# 1_uC.net
KiCad netlist of a schematic drawn in Altium Designer
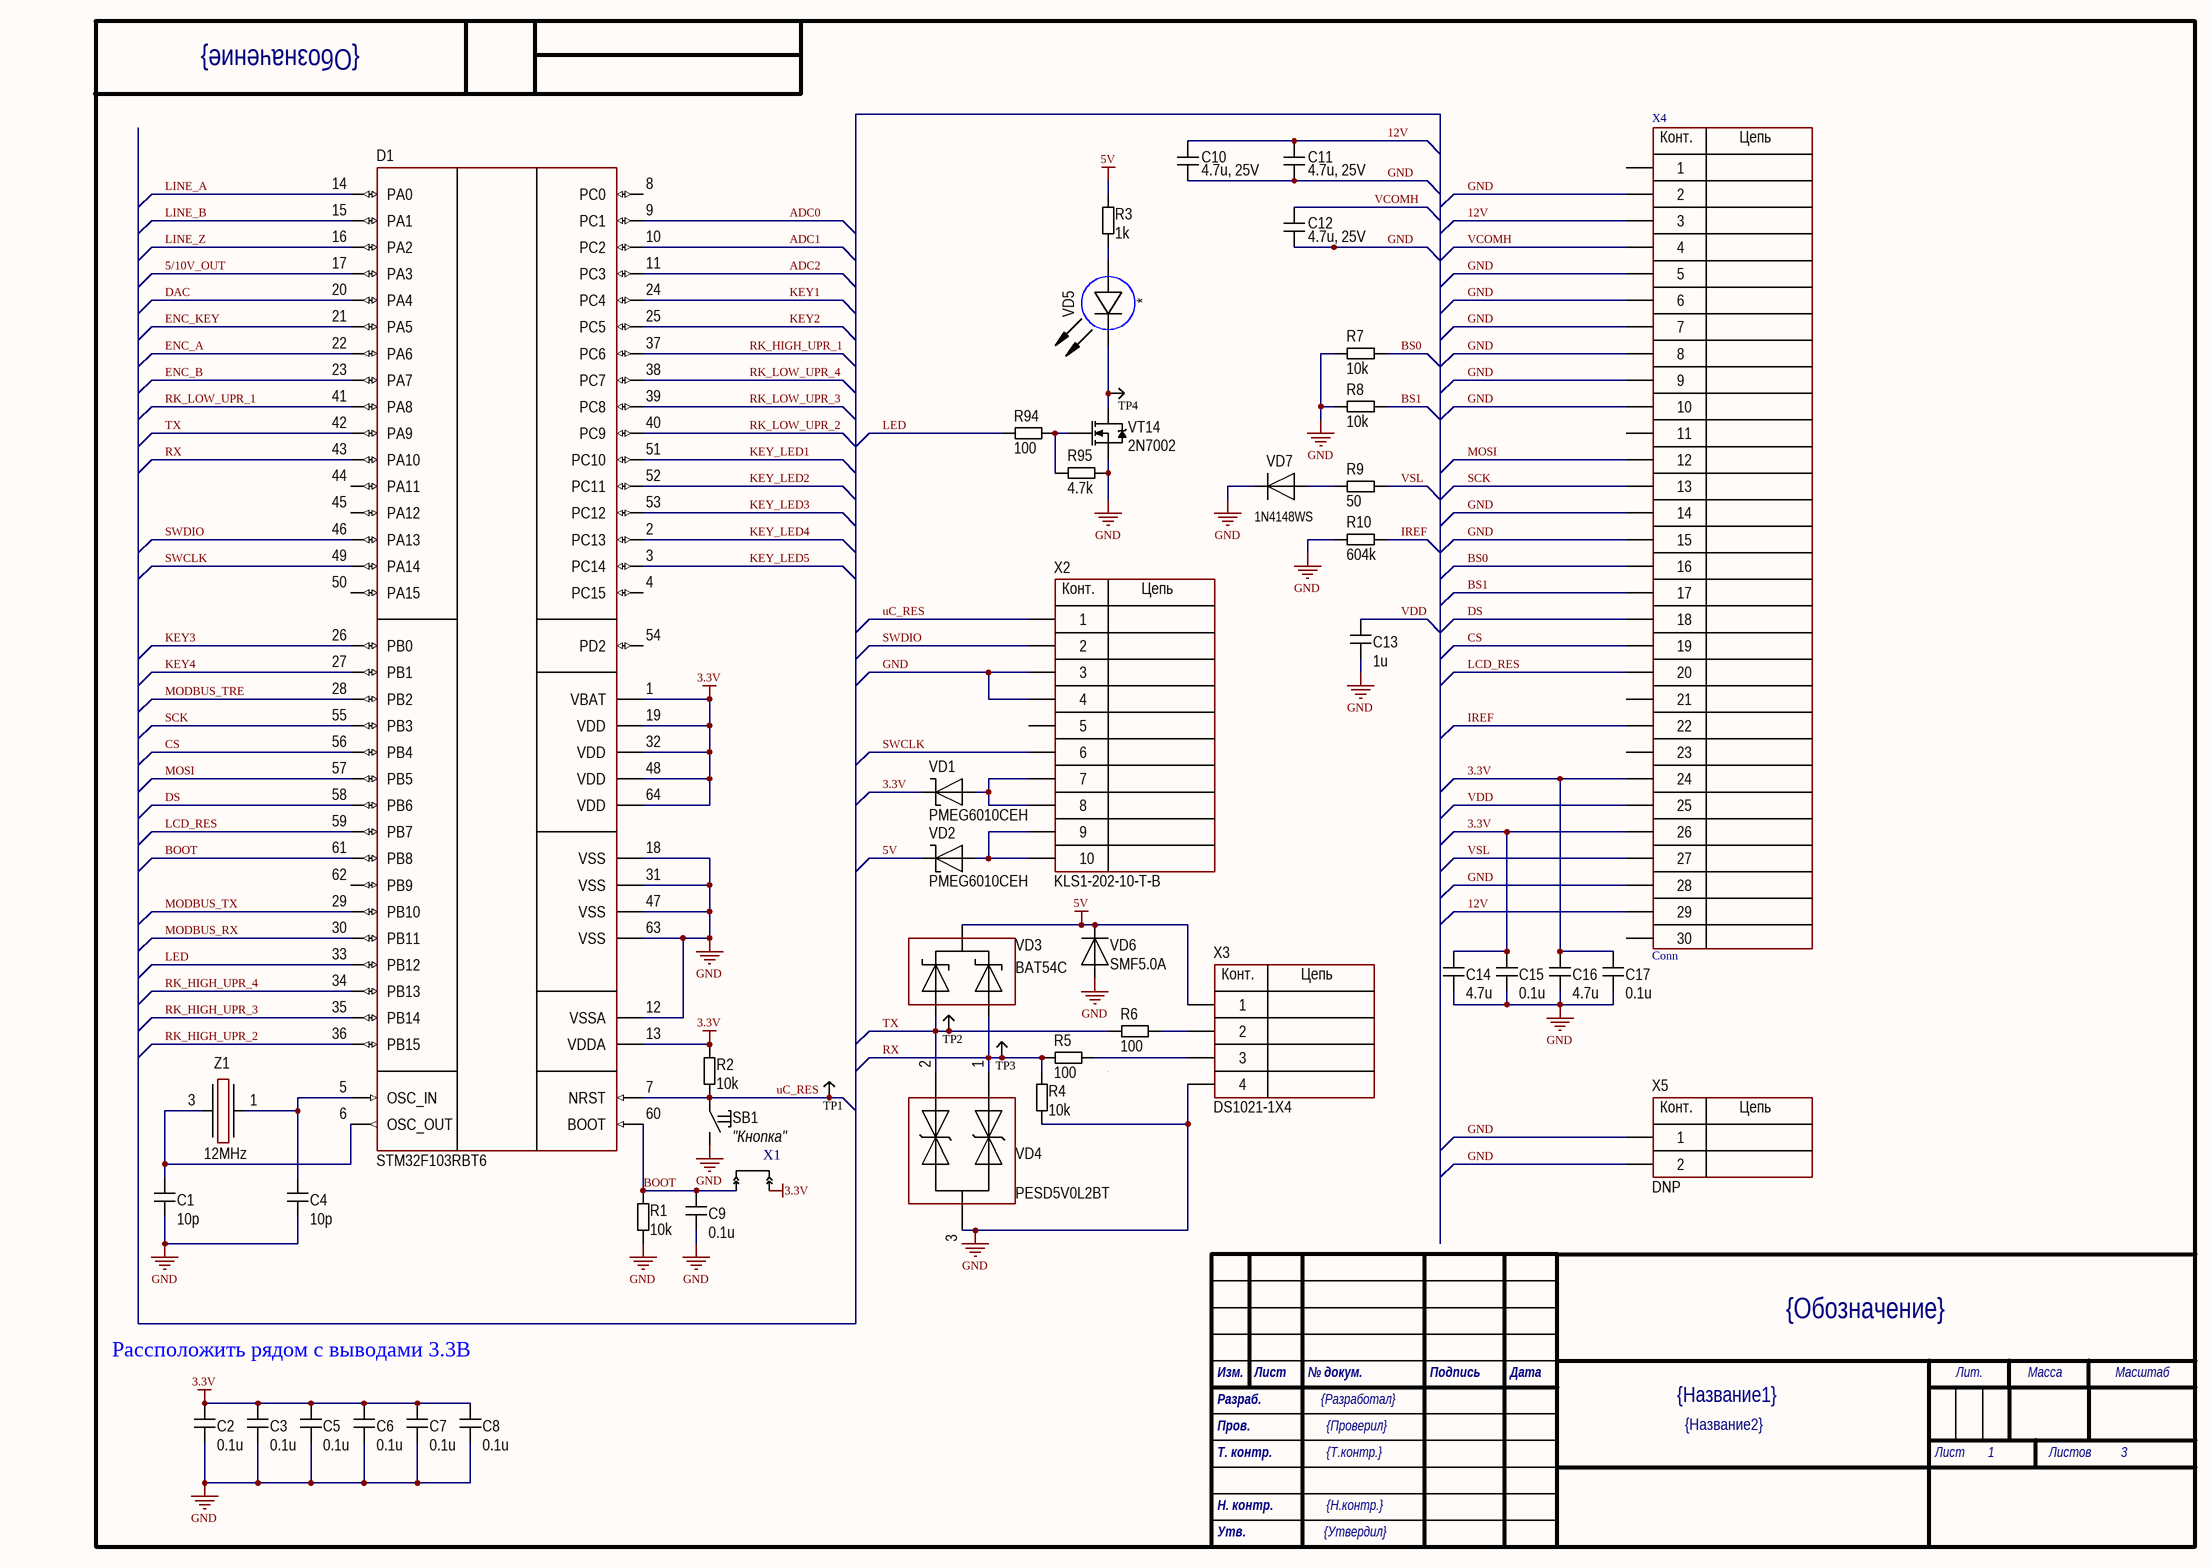
[diagram p0: 1_uC.SchDoc]

(export (version "E")
  (design (tool "Eeschema 10.0.6"))
  (components
    (comp (ref "C1") (value "10p") (footprint "CH0402C") (libsource (lib "Condensators") (part "Capacitor")))
    (comp (ref "C2") (value "0.1u") (footprint "CH0603C") (libsource (lib "Condensators") (part "Capacitor")))
    (comp (ref "C3") (value "0.1u") (footprint "CH0603C") (libsource (lib "Condensators") (part "Capacitor")))
    (comp (ref "C4") (value "10p") (footprint "CH0402C") (libsource (lib "Condensators") (part "Capacitor")))
    (comp (ref "C5") (value "0.1u") (footprint "CH0603C") (libsource (lib "Condensators") (part "Capacitor")))
    (comp (ref "C6") (value "0.1u") (footprint "CH0603C") (libsource (lib "Condensators") (part "Capacitor")))
    (comp (ref "C7") (value "0.1u") (footprint "CH0603C") (libsource (lib "Condensators") (part "Capacitor")))
    (comp (ref "C8") (value "0.1u") (footprint "CH0603C") (libsource (lib "Condensators") (part "Capacitor")))
    (comp (ref "C9") (value "0.1u") (footprint "CH0603C") (libsource (lib "Condensators") (part "Capacitor")))
    (comp (ref "C10")
      (value "4.7u, 25V")
      (footprint "CH0805C")
      (libsource (lib "Condensators") (part "Capacitor"))
    )
    (comp (ref "C11")
      (value "4.7u, 25V")
      (footprint "CH0805C")
      (libsource (lib "Condensators") (part "Capacitor"))
    )
    (comp (ref "C12")
      (value "4.7u, 25V")
      (footprint "CH0805C")
      (libsource (lib "Condensators") (part "Capacitor"))
    )
    (comp (ref "C13") (value "1u") (footprint "CH0603C") (libsource (lib "Condensators") (part "Capacitor")))
    (comp (ref "C14")
      (value "4.7u")
      (footprint "CH0603C")
      (libsource (lib "Condensators") (part "Capacitor"))
    )
    (comp (ref "C15")
      (value "0.1u")
      (footprint "CH0603C")
      (libsource (lib "Condensators") (part "Capacitor"))
    )
    (comp (ref "C16")
      (value "4.7u")
      (footprint "CH0603C")
      (libsource (lib "Condensators") (part "Capacitor"))
    )
    (comp (ref "C17")
      (value "0.1u")
      (footprint "CH0603C")
      (libsource (lib "Condensators") (part "Capacitor"))
    )
    (comp (ref "D1")
      (value "STM32F103RBT6")
      (footprint "64-LQFP")
      (description "Cortex-M3")
      (fields (field (name "MANUFACTURER") "STMicroelectronics"))
      (libsource (lib "MicroIC") (part "STM32F103RBT6"))
    )
    (comp (ref "R1") (value "10k") (footprint "CH0603R") (libsource (lib "Resistors") (part "Resistor")))
    (comp (ref "R2") (value "10k") (footprint "CH0603R") (libsource (lib "Resistors") (part "Resistor")))
    (comp (ref "R3") (value "1k") (footprint "CH0805R") (libsource (lib "Resistors") (part "Resistor")))
    (comp (ref "R4") (value "10k") (footprint "CH0603R") (libsource (lib "Resistors") (part "Resistor")))
    (comp (ref "R5") (value "100") (footprint "CH0603R") (libsource (lib "Resistors") (part "Resistor")))
    (comp (ref "R6") (value "100") (footprint "CH0603R") (libsource (lib "Resistors") (part "Resistor")))
    (comp (ref "R7") (value "10k") (footprint "CH0603R") (libsource (lib "Resistors") (part "Resistor")))
    (comp (ref "R8") (value "10k") (footprint "CH0603R") (libsource (lib "Resistors") (part "Resistor")))
    (comp (ref "R9") (value "50") (footprint "CH0603R") (libsource (lib "Resistors") (part "Resistor")))
    (comp (ref "R10") (value "604k") (footprint "CH0603R") (libsource (lib "Resistors") (part "Resistor")))
    (comp (ref "R94") (value "100") (footprint "CH0603R") (libsource (lib "Resistors") (part "Resistor")))
    (comp (ref "R95") (value "4.7k") (footprint "CH0603R") (libsource (lib "Resistors") (part "Resistor")))
    (comp (ref "SB1")
      (value "\"Кнопка\"")
      (footprint "TL1014BF160QG")
      (description "6x6 mm")
      (libsource (lib "Connectors") (part "Tactile switches"))
    )
    (comp (ref "TP1") (value "~") (footprint "TestPoint") (libsource (lib "Melochi") (part "TestPoint")))
    (comp (ref "TP2") (value "~") (footprint "TestPoint") (libsource (lib "Melochi") (part "TestPoint")))
    (comp (ref "TP3") (value "~") (footprint "TestPoint") (libsource (lib "Melochi") (part "TestPoint")))
    (comp (ref "TP4") (value "~") (footprint "TestPoint") (libsource (lib "Melochi") (part "TestPoint")))
    (comp (ref "VD1")
      (value "PMEG6010CEH")
      (footprint "SOD123F")
      (libsource (lib "Diods") (part "Diod Schottky"))
    )
    (comp (ref "VD2")
      (value "PMEG6010CEH")
      (footprint "SOD123F")
      (libsource (lib "Diods") (part "Diod Schottky"))
    )
    (comp (ref "VD3")
      (value "BAT54C")
      (footprint "SOT23_123")
      (libsource (lib "Diods") (part "Diod Schottky Array v.1"))
    )
    (comp (ref "VD4")
      (value "PESD5V0L2BT")
      (footprint "SOT23_132")
      (libsource (lib "Diods") (part "TVS Array"))
    )
    (comp (ref "VD5") (value "*") (footprint "CH0603LB") (libsource (lib "Diods") (part "LED_1")))
    (comp (ref "VD6")
      (value "SMF5.0A")
      (footprint "SOD123F")
      (fields (field (name "PART NUM") "SMAF5.0A"))
      (libsource (lib "Diods") (part "Diod"))
    )
    (comp (ref "VD7") (value "1N4148WS") (footprint "SOD323") (libsource (lib "Diods") (part "Diod")))
    (comp (ref "VT14")
      (value "2N7002")
      (footprint "SOT23_123")
      (description "Mosfet")
      (libsource (lib "Tranzistor") (part "N-chanel"))
    )
    (comp (ref "X1") (value "JMP-2") (footprint "PLS-2") (libsource (lib "Connectors") (part "JMP-2")))
    (comp (ref "X2")
      (value "KLS1-202-10-T-B")
      (footprint "CON: IDC-10MS")
      (libsource (lib "Connectors") (part "10-Connector"))
    )
    (comp (ref "X3")
      (value "DS1021-1X4")
      (footprint "CON: PLS-4")
      (libsource (lib "Connectors") (part "4-Connector"))
    )
    (comp (ref "X4") (value "Conn") (footprint "FPC-30") (libsource (lib "Connectors") (part "30-Connector")))
    (comp (ref "X5")
      (value "DNP")
      (footprint "CON: PLS-2")
      (libsource (lib "Connectors") (part "2-Connector"))
    )
    (comp (ref "Z1") (value "12MHz") (footprint "OSC: 2520") (libsource (lib "Melochi") (part "Oscillator")))
  )
  (nets
    (net (code "1") (name "/5{slash}10V_OUT") (class "Default")
      (node (ref "D1") (pin "17") (pinfunction "PA3_17") (pintype "bidirectional"))
    )
    (net (code "2") (name "/12V") (class "Default")
      (node (ref "C10") (pin "2") (pinfunction "2_2") (pintype "passive"))
      (node (ref "C11") (pin "2") (pinfunction "2_2") (pintype "passive"))
      (node (ref "X4") (pin "29") (pinfunction "29_29") (pintype "power_in"))
      (node (ref "X4") (pin "3") (pinfunction "3_3") (pintype "power_in"))
    )
    (net (code "3") (name "/ADC0") (class "Default")
      (node (ref "D1") (pin "9") (pinfunction "PC1_9") (pintype "bidirectional"))
    )
    (net (code "4") (name "/ADC1") (class "Default")
      (node (ref "D1") (pin "10") (pinfunction "PC2_10") (pintype "bidirectional"))
    )
    (net (code "5") (name "/ADC2") (class "Default")
      (node (ref "D1") (pin "11") (pinfunction "PC3_11") (pintype "bidirectional"))
    )
    (net (code "6") (name "/BOOT") (class "Default")
      (node (ref "C9") (pin "2") (pinfunction "2_2") (pintype "passive"))
      (node (ref "D1") (pin "60") (pinfunction "BOOT_60") (pintype "input"))
      (node (ref "D1") (pin "61") (pinfunction "PB8_61") (pintype "bidirectional"))
      (node (ref "R1") (pin "2") (pinfunction "2_2") (pintype "passive"))
      (node (ref "X1") (pin "1") (pinfunction "1_1") (pintype "passive"))
    )
    (net (code "7") (name "/BS0") (class "Default")
      (node (ref "R7") (pin "2") (pinfunction "2_2") (pintype "passive"))
      (node (ref "X4") (pin "16") (pinfunction "16_16") (pintype "power_in"))
    )
    (net (code "8") (name "/BS1") (class "Default")
      (node (ref "R8") (pin "2") (pinfunction "2_2") (pintype "passive"))
      (node (ref "X4") (pin "17") (pinfunction "17_17") (pintype "power_in"))
    )
    (net (code "9") (name "/CS") (class "Default")
      (node (ref "D1") (pin "56") (pinfunction "PB4_56") (pintype "bidirectional"))
      (node (ref "X4") (pin "19") (pinfunction "19_19") (pintype "power_in"))
    )
    (net (code "10") (name "/DAC") (class "Default")
      (node (ref "D1") (pin "20") (pinfunction "PA4_20") (pintype "bidirectional"))
    )
    (net (code "11") (name "/DS") (class "Default")
      (node (ref "D1") (pin "58") (pinfunction "PB6_58") (pintype "bidirectional"))
      (node (ref "X4") (pin "18") (pinfunction "18_18") (pintype "power_in"))
    )
    (net (code "12") (name "/ENC_A") (class "Default")
      (node (ref "D1") (pin "22") (pinfunction "PA6_22") (pintype "bidirectional"))
    )
    (net (code "13") (name "/ENC_B") (class "Default")
      (node (ref "D1") (pin "23") (pinfunction "PA7_23") (pintype "bidirectional"))
    )
    (net (code "14") (name "/ENC_KEY") (class "Default")
      (node (ref "D1") (pin "21") (pinfunction "PA5_21") (pintype "bidirectional"))
    )
    (net (code "15") (name "/IREF") (class "Default")
      (node (ref "R10") (pin "2") (pinfunction "2_2") (pintype "passive"))
      (node (ref "X4") (pin "22") (pinfunction "22_22") (pintype "passive"))
    )
    (net (code "16") (name "/KEY1") (class "Default")
      (node (ref "D1") (pin "24") (pinfunction "PC4_24") (pintype "bidirectional"))
    )
    (net (code "17") (name "/KEY2") (class "Default")
      (node (ref "D1") (pin "25") (pinfunction "PC5_25") (pintype "bidirectional"))
    )
    (net (code "18") (name "/KEY3") (class "Default")
      (node (ref "D1") (pin "26") (pinfunction "PB0_26") (pintype "bidirectional"))
    )
    (net (code "19") (name "/KEY4") (class "Default")
      (node (ref "D1") (pin "27") (pinfunction "PB1_27") (pintype "bidirectional"))
    )
    (net (code "20") (name "/KEY_LED1") (class "Default")
      (node (ref "D1") (pin "51") (pinfunction "PC10_51") (pintype "bidirectional"))
    )
    (net (code "21") (name "/KEY_LED2") (class "Default")
      (node (ref "D1") (pin "52") (pinfunction "PC11_52") (pintype "bidirectional"))
    )
    (net (code "22") (name "/KEY_LED3") (class "Default")
      (node (ref "D1") (pin "53") (pinfunction "PC12_53") (pintype "bidirectional"))
    )
    (net (code "23") (name "/KEY_LED4") (class "Default")
      (node (ref "D1") (pin "2") (pinfunction "PC13_2") (pintype "bidirectional"))
    )
    (net (code "24") (name "/KEY_LED5") (class "Default")
      (node (ref "D1") (pin "3") (pinfunction "PC14_3") (pintype "bidirectional"))
    )
    (net (code "25") (name "/LCD_RES") (class "Default")
      (node (ref "D1") (pin "59") (pinfunction "PB7_59") (pintype "bidirectional"))
      (node (ref "X4") (pin "20") (pinfunction "20_20") (pintype "power_in"))
    )
    (net (code "26") (name "/LED") (class "Default")
      (node (ref "D1") (pin "33") (pinfunction "PB12_33") (pintype "bidirectional"))
      (node (ref "R94") (pin "2") (pinfunction "2_2") (pintype "passive"))
    )
    (net (code "27") (name "/LINE_A") (class "Default")
      (node (ref "D1") (pin "14") (pinfunction "PA0_14") (pintype "bidirectional"))
    )
    (net (code "28") (name "/LINE_B") (class "Default")
      (node (ref "D1") (pin "15") (pinfunction "PA1_15") (pintype "bidirectional"))
    )
    (net (code "29") (name "/LINE_Z") (class "Default")
      (node (ref "D1") (pin "16") (pinfunction "PA2_16") (pintype "bidirectional"))
    )
    (net (code "30") (name "/MODBUS_RX") (class "Default")
      (node (ref "D1") (pin "30") (pinfunction "PB11_30") (pintype "bidirectional"))
    )
    (net (code "31") (name "/MODBUS_TRE") (class "Default")
      (node (ref "D1") (pin "28") (pinfunction "PB2_28") (pintype "bidirectional"))
    )
    (net (code "32") (name "/MODBUS_TX") (class "Default")
      (node (ref "D1") (pin "29") (pinfunction "PB10_29") (pintype "bidirectional"))
    )
    (net (code "33") (name "/MOSI") (class "Default")
      (node (ref "D1") (pin "57") (pinfunction "PB5_57") (pintype "bidirectional"))
      (node (ref "X4") (pin "12") (pinfunction "12_12") (pintype "passive"))
    )
    (net (code "34") (name "/RK_HIGH_UPR_1") (class "Default")
      (node (ref "D1") (pin "37") (pinfunction "PC6_37") (pintype "bidirectional"))
    )
    (net (code "35") (name "/RK_HIGH_UPR_2") (class "Default")
      (node (ref "D1") (pin "36") (pinfunction "PB15_36") (pintype "bidirectional"))
    )
    (net (code "36") (name "/RK_HIGH_UPR_3") (class "Default")
      (node (ref "D1") (pin "35") (pinfunction "PB14_35") (pintype "bidirectional"))
    )
    (net (code "37") (name "/RK_HIGH_UPR_4") (class "Default")
      (node (ref "D1") (pin "34") (pinfunction "PB13_34") (pintype "bidirectional"))
    )
    (net (code "38") (name "/RK_LOW_UPR_1") (class "Default")
      (node (ref "D1") (pin "41") (pinfunction "PA8_41") (pintype "bidirectional"))
    )
    (net (code "39") (name "/RK_LOW_UPR_2") (class "Default")
      (node (ref "D1") (pin "40") (pinfunction "PC9_40") (pintype "bidirectional"))
    )
    (net (code "40") (name "/RK_LOW_UPR_3") (class "Default")
      (node (ref "D1") (pin "39") (pinfunction "PC8_39") (pintype "bidirectional"))
    )
    (net (code "41") (name "/RK_LOW_UPR_4") (class "Default")
      (node (ref "D1") (pin "38") (pinfunction "PC7_38") (pintype "bidirectional"))
    )
    (net (code "42") (name "/RX") (class "Default")
      (node (ref "D1") (pin "43") (pinfunction "PA10_43") (pintype "bidirectional"))
      (node (ref "R4") (pin "1") (pinfunction "1_1") (pintype "passive"))
      (node (ref "R5") (pin "2") (pinfunction "2_2") (pintype "passive"))
      (node (ref "TP3") (pin "0") (pinfunction "0_0") (pintype "passive"))
      (node (ref "VD3") (pin "1") (pinfunction "1_1") (pintype "passive"))
      (node (ref "VD4") (pin "1") (pintype "passive"))
    )
    (net (code "43") (name "/SCK") (class "Default")
      (node (ref "D1") (pin "55") (pinfunction "PB3_55") (pintype "bidirectional"))
      (node (ref "X4") (pin "13") (pinfunction "13_13") (pintype "power_in"))
    )
    (net (code "44") (name "/SWCLK") (class "Default")
      (node (ref "D1") (pin "49") (pinfunction "PA14_49") (pintype "bidirectional"))
      (node (ref "X2") (pin "6") (pinfunction "6_6") (pintype "power_in"))
    )
    (net (code "45") (name "/SWDIO") (class "Default")
      (node (ref "D1") (pin "46") (pinfunction "PA13_46") (pintype "bidirectional"))
      (node (ref "X2") (pin "2") (pinfunction "2_2") (pintype "passive"))
    )
    (net (code "46") (name "/TX") (class "Default")
      (node (ref "D1") (pin "42") (pinfunction "PA9_42") (pintype "bidirectional"))
      (node (ref "R6") (pin "2") (pinfunction "2_2") (pintype "passive"))
      (node (ref "TP2") (pin "0") (pinfunction "0_0") (pintype "passive"))
      (node (ref "VD3") (pin "3") (pinfunction "3_3") (pintype "passive"))
      (node (ref "VD4") (pin "2") (pintype "passive"))
    )
    (net (code "47") (name "/VCOMH") (class "Default")
      (node (ref "C12") (pin "2") (pinfunction "2_2") (pintype "passive"))
      (node (ref "X4") (pin "4") (pinfunction "4_4") (pintype "power_in"))
    )
    (net (code "48") (name "/VDD") (class "Default")
      (node (ref "C13") (pin "2") (pinfunction "2_2") (pintype "passive"))
      (node (ref "X4") (pin "25") (pinfunction "25_25") (pintype "power_in"))
    )
    (net (code "49") (name "/VSL") (class "Default")
      (node (ref "R9") (pin "2") (pinfunction "2_2") (pintype "passive"))
      (node (ref "X4") (pin "27") (pinfunction "27_27") (pintype "power_in"))
    )
    (net (code "50") (name "/uC_RES") (class "Default")
      (node (ref "D1") (pin "7") (pinfunction "NRST_7") (pintype "input"))
      (node (ref "R2") (pin "1") (pinfunction "1_1") (pintype "passive"))
      (node (ref "SB1") (pin "1") (pinfunction "1_1") (pintype "passive"))
      (node (ref "TP1") (pin "0") (pinfunction "0_0") (pintype "passive"))
      (node (ref "X2") (pin "1") (pinfunction "1_1") (pintype "passive"))
    )
    (net (code "51") (name "3.3V") (class "Default")
      (node (ref "C14") (pin "2") (pinfunction "2_2") (pintype "passive"))
      (node (ref "C15") (pin "2") (pinfunction "2_2") (pintype "passive"))
      (node (ref "C16") (pin "2") (pinfunction "2_2") (pintype "passive"))
      (node (ref "C17") (pin "2") (pinfunction "2_2") (pintype "passive"))
      (node (ref "C2") (pin "2") (pinfunction "2_2") (pintype "passive"))
      (node (ref "C3") (pin "2") (pinfunction "2_2") (pintype "passive"))
      (node (ref "C5") (pin "2") (pinfunction "2_2") (pintype "passive"))
      (node (ref "C6") (pin "2") (pinfunction "2_2") (pintype "passive"))
      (node (ref "C7") (pin "2") (pinfunction "2_2") (pintype "passive"))
      (node (ref "C8") (pin "2") (pinfunction "2_2") (pintype "passive"))
      (node (ref "D1") (pin "1") (pinfunction "VBAT_1") (pintype "power_in"))
      (node (ref "D1") (pin "13") (pinfunction "VDDA_13") (pintype "power_in"))
      (node (ref "D1") (pin "19") (pinfunction "VDD_19") (pintype "power_in"))
      (node (ref "D1") (pin "32") (pinfunction "VDD_32") (pintype "power_in"))
      (node (ref "D1") (pin "48") (pinfunction "VDD_48") (pintype "power_in"))
      (node (ref "D1") (pin "64") (pinfunction "VDD_64") (pintype "power_in"))
      (node (ref "R2") (pin "2") (pinfunction "2_2") (pintype "passive"))
      (node (ref "VD1") (pin "2") (pinfunction "2_2") (pintype "passive"))
      (node (ref "X1") (pin "2") (pinfunction "2_2") (pintype "passive"))
      (node (ref "X4") (pin "24") (pinfunction "24_24") (pintype "power_in"))
      (node (ref "X4") (pin "26") (pinfunction "26_26") (pintype "power_in"))
    )
    (net (code "52") (name "5V") (class "Default")
      (node (ref "R3") (pin "2") (pinfunction "2_2") (pintype "passive"))
      (node (ref "VD2") (pin "2") (pinfunction "2_2") (pintype "passive"))
      (node (ref "VD3") (pin "2") (pinfunction "2_2") (pintype "passive"))
      (node (ref "VD6") (pin "2") (pinfunction "2_2") (pintype "passive"))
      (node (ref "X3") (pin "1") (pinfunction "1_1") (pintype "passive"))
    )
    (net (code "53") (name "GND") (class "Default")
      (node (ref "C1") (pin "1") (pinfunction "1_1") (pintype "passive"))
      (node (ref "C10") (pin "1") (pinfunction "1_1") (pintype "passive"))
      (node (ref "C11") (pin "1") (pinfunction "1_1") (pintype "passive"))
      (node (ref "C12") (pin "1") (pinfunction "1_1") (pintype "passive"))
      (node (ref "C13") (pin "1") (pinfunction "1_1") (pintype "passive"))
      (node (ref "C14") (pin "1") (pinfunction "1_1") (pintype "passive"))
      (node (ref "C15") (pin "1") (pinfunction "1_1") (pintype "passive"))
      (node (ref "C16") (pin "1") (pinfunction "1_1") (pintype "passive"))
      (node (ref "C17") (pin "1") (pinfunction "1_1") (pintype "passive"))
      (node (ref "C2") (pin "1") (pinfunction "1_1") (pintype "passive"))
      (node (ref "C3") (pin "1") (pinfunction "1_1") (pintype "passive"))
      (node (ref "C4") (pin "1") (pinfunction "1_1") (pintype "passive"))
      (node (ref "C5") (pin "1") (pinfunction "1_1") (pintype "passive"))
      (node (ref "C6") (pin "1") (pinfunction "1_1") (pintype "passive"))
      (node (ref "C7") (pin "1") (pinfunction "1_1") (pintype "passive"))
      (node (ref "C8") (pin "1") (pinfunction "1_1") (pintype "passive"))
      (node (ref "C9") (pin "1") (pinfunction "1_1") (pintype "passive"))
      (node (ref "D1") (pin "12") (pinfunction "VSSA_12") (pintype "power_in"))
      (node (ref "D1") (pin "18") (pinfunction "VSS_18") (pintype "power_in"))
      (node (ref "D1") (pin "31") (pinfunction "VSS_31") (pintype "power_in"))
      (node (ref "D1") (pin "47") (pinfunction "VSS_47") (pintype "power_in"))
      (node (ref "D1") (pin "63") (pinfunction "VSS_63") (pintype "power_in"))
      (node (ref "R1") (pin "1") (pinfunction "1_1") (pintype "passive"))
      (node (ref "R10") (pin "1") (pinfunction "1_1") (pintype "passive"))
      (node (ref "R4") (pin "2") (pinfunction "2_2") (pintype "passive"))
      (node (ref "R7") (pin "1") (pinfunction "1_1") (pintype "passive"))
      (node (ref "R8") (pin "1") (pinfunction "1_1") (pintype "passive"))
      (node (ref "R95") (pin "1") (pinfunction "1_1") (pintype "passive"))
      (node (ref "SB1") (pin "2") (pinfunction "2_2") (pintype "passive"))
      (node (ref "VD4") (pin "3") (pintype "passive"))
      (node (ref "VD6") (pin "1") (pinfunction "1_1") (pintype "passive"))
      (node (ref "VD7") (pin "2") (pinfunction "2_2") (pintype "passive"))
      (node (ref "VT14") (pin "3") (pinfunction "S_3") (pintype "passive"))
      (node (ref "X2") (pin "3") (pinfunction "3_3") (pintype "power_in"))
      (node (ref "X2") (pin "4") (pinfunction "4_4") (pintype "power_in"))
      (node (ref "X3") (pin "4") (pinfunction "4_4") (pintype "power_in"))
      (node (ref "X4") (pin "10") (pinfunction "10_10") (pintype "power_in"))
      (node (ref "X4") (pin "14") (pinfunction "14_14") (pintype "power_in"))
      (node (ref "X4") (pin "15") (pinfunction "15_15") (pintype "power_in"))
      (node (ref "X4") (pin "2") (pinfunction "2_2") (pintype "passive"))
      (node (ref "X4") (pin "28") (pinfunction "28_28") (pintype "power_in"))
      (node (ref "X4") (pin "5") (pinfunction "5_5") (pintype "power_in"))
      (node (ref "X4") (pin "6") (pinfunction "6_6") (pintype "power_in"))
      (node (ref "X4") (pin "7") (pinfunction "7_7") (pintype "power_in"))
      (node (ref "X4") (pin "8") (pinfunction "8_8") (pintype "power_in"))
      (node (ref "X4") (pin "9") (pinfunction "9_9") (pintype "power_in"))
      (node (ref "X5") (pin "1") (pinfunction "1_1") (pintype "passive"))
      (node (ref "X5") (pin "2") (pinfunction "2_2") (pintype "passive"))
    )
    (net (code "54") (name "Net-(D1-OSC_IN)") (class "Default")
      (node (ref "C4") (pin "2") (pinfunction "2_2") (pintype "passive"))
      (node (ref "D1") (pin "5") (pinfunction "OSC_IN_5") (pintype "input"))
      (node (ref "Z1") (pin "1") (pinfunction "1_1") (pintype "passive"))
    )
    (net (code "55") (name "Net-(D1-OSC_OUT)") (class "Default")
      (node (ref "C1") (pin "2") (pinfunction "2_2") (pintype "passive"))
      (node (ref "D1") (pin "6") (pinfunction "OSC_OUT_6") (pintype "output"))
      (node (ref "Z1") (pin "3") (pinfunction "3_3") (pintype "passive"))
    )
    (net (code "56") (name "Net-(R5-Pad1)") (class "Default")
      (node (ref "R5") (pin "1") (pinfunction "1_1") (pintype "passive"))
      (node (ref "X3") (pin "3") (pinfunction "3_3") (pintype "power_in"))
    )
    (net (code "57") (name "Net-(R6-Pad1)") (class "Default")
      (node (ref "R6") (pin "1") (pinfunction "1_1") (pintype "passive"))
      (node (ref "X3") (pin "2") (pinfunction "2_2") (pintype "passive"))
    )
    (net (code "58") (name "Net-(R9-Pad1)") (class "Default")
      (node (ref "R9") (pin "1") (pinfunction "1_1") (pintype "passive"))
      (node (ref "VD7") (pin "1") (pinfunction "1_1") (pintype "passive"))
    )
    (net (code "59") (name "Net-(VD1-Pad1)") (class "Default")
      (node (ref "VD1") (pin "1") (pinfunction "1_1") (pintype "passive"))
      (node (ref "X2") (pin "7") (pinfunction "7_7") (pintype "power_in"))
      (node (ref "X2") (pin "8") (pinfunction "8_8") (pintype "power_in"))
    )
    (net (code "60") (name "Net-(VD2-Pad1)") (class "Default")
      (node (ref "VD2") (pin "1") (pinfunction "1_1") (pintype "passive"))
      (node (ref "X2") (pin "10") (pinfunction "10_10") (pintype "power_in"))
      (node (ref "X2") (pin "9") (pinfunction "9_9") (pintype "power_in"))
    )
    (net (code "61") (name "Net-(VD5-A)") (class "Default")
      (node (ref "R3") (pin "1") (pinfunction "1_1") (pintype "passive"))
      (node (ref "VD5") (pin "1") (pinfunction "A_1") (pintype "passive"))
    )
    (net (code "62") (name "Net-(VD5-C)") (class "Default")
      (node (ref "TP4") (pin "0") (pinfunction "0_0") (pintype "passive"))
      (node (ref "VD5") (pin "2") (pinfunction "C_2") (pintype "passive"))
      (node (ref "VT14") (pin "2") (pinfunction "D_2") (pintype "passive"))
    )
    (net (code "63") (name "Net-(VT14-G)") (class "Default")
      (node (ref "R94") (pin "1") (pinfunction "1_1") (pintype "passive"))
      (node (ref "R95") (pin "2") (pinfunction "2_2") (pintype "passive"))
      (node (ref "VT14") (pin "1") (pinfunction "G_1") (pintype "passive"))
    )
    (net (code "64") (name "unconnected-(D1-PA11-Pad44)") (class "Default")
      (node (ref "D1") (pin "44") (pinfunction "PA11_44") (pintype "bidirectional"))
    )
    (net (code "65") (name "unconnected-(D1-PA12-Pad45)") (class "Default")
      (node (ref "D1") (pin "45") (pinfunction "PA12_45") (pintype "bidirectional"))
    )
    (net (code "66") (name "unconnected-(D1-PA15-Pad50)") (class "Default")
      (node (ref "D1") (pin "50") (pinfunction "PA15_50") (pintype "bidirectional"))
    )
    (net (code "67") (name "unconnected-(D1-PB9-Pad62)") (class "Default")
      (node (ref "D1") (pin "62") (pinfunction "PB9_62") (pintype "bidirectional"))
    )
    (net (code "68") (name "unconnected-(D1-PC0-Pad8)") (class "Default")
      (node (ref "D1") (pin "8") (pinfunction "PC0_8") (pintype "bidirectional"))
    )
    (net (code "69") (name "unconnected-(D1-PC15-Pad4)") (class "Default")
      (node (ref "D1") (pin "4") (pinfunction "PC15_4") (pintype "bidirectional"))
    )
    (net (code "70") (name "unconnected-(D1-PD2-Pad54)") (class "Default")
      (node (ref "D1") (pin "54") (pinfunction "PD2_54") (pintype "bidirectional"))
    )
    (net (code "71") (name "unconnected-(X2-Pad5)") (class "Default")
      (node (ref "X2") (pin "5") (pinfunction "5_5") (pintype "power_in"))
    )
    (net (code "72") (name "unconnected-(X4-Pad1)") (class "Default")
      (node (ref "X4") (pin "1") (pinfunction "1_1") (pintype "passive"))
    )
    (net (code "73") (name "unconnected-(X4-Pad11)") (class "Default")
      (node (ref "X4") (pin "11") (pinfunction "11_11") (pintype "passive"))
    )
    (net (code "74") (name "unconnected-(X4-Pad21)") (class "Default")
      (node (ref "X4") (pin "21") (pinfunction "21_21") (pintype "passive"))
    )
    (net (code "75") (name "unconnected-(X4-Pad23)") (class "Default")
      (node (ref "X4") (pin "23") (pinfunction "23_23") (pintype "power_in"))
    )
    (net (code "76") (name "unconnected-(X4-Pad30)") (class "Default")
      (node (ref "X4") (pin "30") (pinfunction "30_30") (pintype "power_in"))
    )
  )
)
